# AgnusAdaptorEagle7.net
KiCad netlist of a schematic drawn in EAGLE
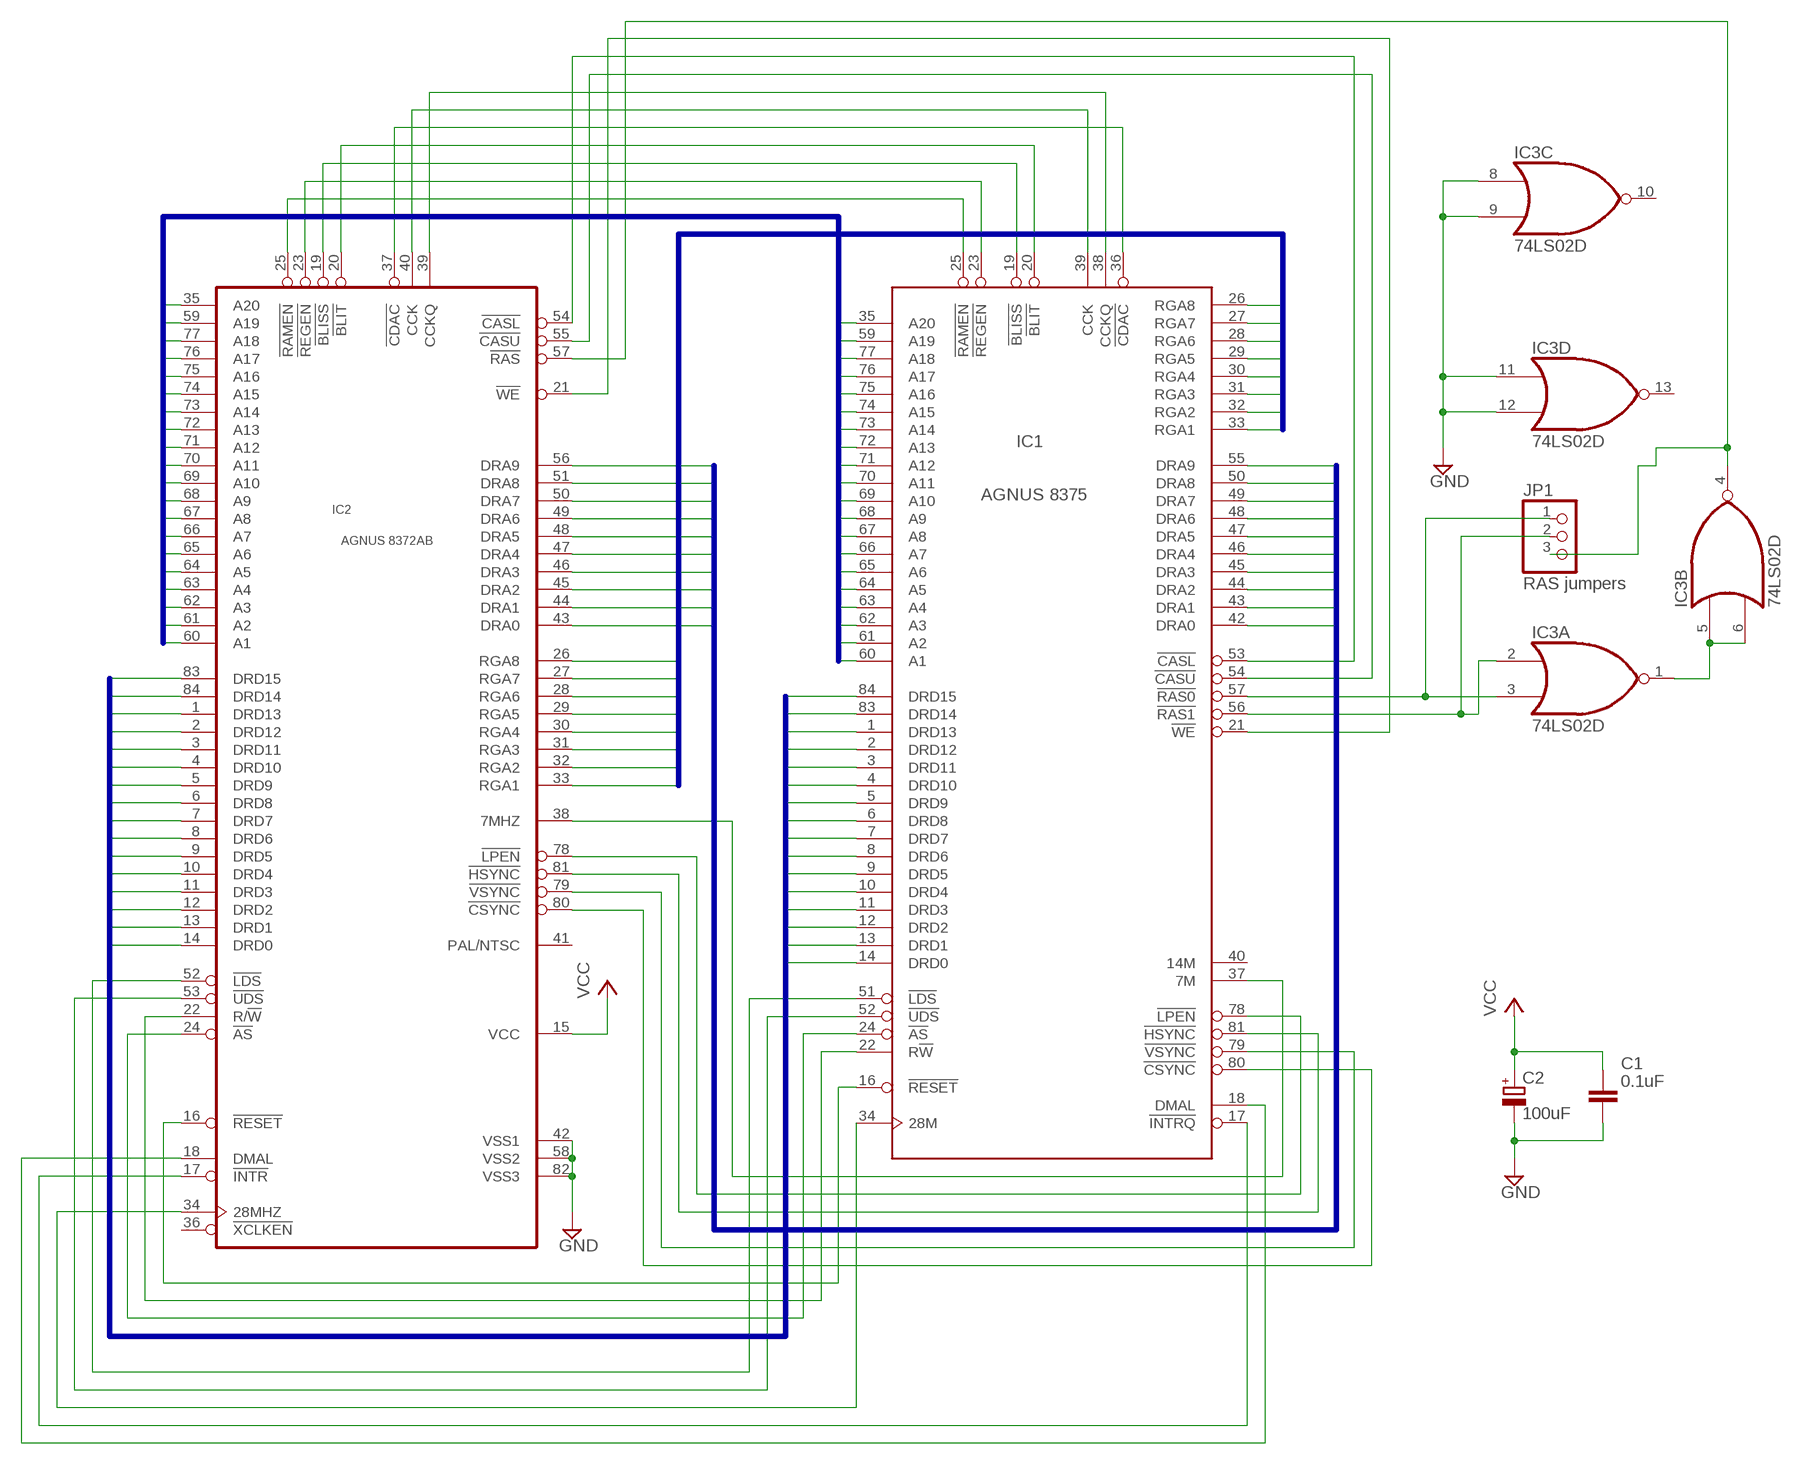
[diagram p0: schematic, sheet 1]

(export (version "E")
  (design (tool "Eeschema 10.0.6"))
  (components
    (comp (ref "C1")
      (value "0.1uF")
      (footprint "eagle-import:CAPC2012X110")
      (libsource (lib "eagle-import") (part "CCHIP-0805(2012-METRIC)_"))
    )
    (comp (ref "C2")
      (value "100uF")
      (footprint "eagle-import:CAPAE830X1050N")
      (libsource (lib "eagle-import") (part "C-POLECAP-8.5MM_"))
    )
    (comp (ref "IC1")
      (value "AGNUS_8375_A500+_A600_THT")
      (footprint "eagle-import:PLCC84_T")
      (libsource (lib "eagle-import") (part "AGNUS_8375_A500+_A600_THT"))
    )
    (comp (ref "IC2")
      (value "A3000 Agnus Socket")
      (footprint "eagle-import:PLCC84_T")
      (libsource (lib "eagle-import") (part "AGNUS_8372AB_THT"))
    )
    (comp (ref "IC3")
      (value "74LS02D")
      (footprint "eagle-import:SO14")
      (libsource (lib "eagle-import") (part "7402DLS"))
    )
    (comp (ref "JP1")
      (value "RAS jumpers")
      (footprint "eagle-import:1X03")
      (libsource (lib "eagle-import") (part "PINHD-1X3"))
    )
  )
  (nets
    (net (code "1") (name "/A1") (class "Default")
      (node (ref "IC1") (pin "60") (pinfunction "A1_60") (pintype "input"))
      (node (ref "IC2") (pin "60") (pinfunction "A1_60") (pintype "input"))
    )
    (net (code "2") (name "/A2") (class "Default")
      (node (ref "IC1") (pin "61") (pinfunction "A2_61") (pintype "input"))
      (node (ref "IC2") (pin "61") (pinfunction "A2_61") (pintype "input"))
    )
    (net (code "3") (name "/A3") (class "Default")
      (node (ref "IC1") (pin "62") (pinfunction "A3_62") (pintype "input"))
      (node (ref "IC2") (pin "62") (pinfunction "A3_62") (pintype "input"))
    )
    (net (code "4") (name "/A4") (class "Default")
      (node (ref "IC1") (pin "63") (pinfunction "A4_63") (pintype "input"))
      (node (ref "IC2") (pin "63") (pinfunction "A4_63") (pintype "input"))
    )
    (net (code "5") (name "/A5") (class "Default")
      (node (ref "IC1") (pin "64") (pinfunction "A5_64") (pintype "input"))
      (node (ref "IC2") (pin "64") (pinfunction "A5_64") (pintype "input"))
    )
    (net (code "6") (name "/A6") (class "Default")
      (node (ref "IC1") (pin "65") (pinfunction "A6_65") (pintype "input"))
      (node (ref "IC2") (pin "65") (pinfunction "A6_65") (pintype "input"))
    )
    (net (code "7") (name "/A7") (class "Default")
      (node (ref "IC1") (pin "66") (pinfunction "A7_66") (pintype "input"))
      (node (ref "IC2") (pin "66") (pinfunction "A7_66") (pintype "input"))
    )
    (net (code "8") (name "/A8") (class "Default")
      (node (ref "IC1") (pin "67") (pinfunction "A8_67") (pintype "input"))
      (node (ref "IC2") (pin "67") (pinfunction "A8_67") (pintype "input"))
    )
    (net (code "9") (name "/A9") (class "Default")
      (node (ref "IC1") (pin "68") (pinfunction "A9_68") (pintype "input"))
      (node (ref "IC2") (pin "68") (pinfunction "A9_68") (pintype "input"))
    )
    (net (code "10") (name "/A10") (class "Default")
      (node (ref "IC1") (pin "69") (pinfunction "A10_69") (pintype "input"))
      (node (ref "IC2") (pin "69") (pinfunction "A10_69") (pintype "input"))
    )
    (net (code "11") (name "/A11") (class "Default")
      (node (ref "IC1") (pin "70") (pinfunction "A11_70") (pintype "input"))
      (node (ref "IC2") (pin "70") (pinfunction "A11_70") (pintype "input"))
    )
    (net (code "12") (name "/A12") (class "Default")
      (node (ref "IC1") (pin "71") (pinfunction "A12_71") (pintype "input"))
      (node (ref "IC2") (pin "71") (pinfunction "A12_71") (pintype "input"))
    )
    (net (code "13") (name "/A13") (class "Default")
      (node (ref "IC1") (pin "72") (pinfunction "A13_72") (pintype "input"))
      (node (ref "IC2") (pin "72") (pinfunction "A13_72") (pintype "input"))
    )
    (net (code "14") (name "/A14") (class "Default")
      (node (ref "IC1") (pin "73") (pinfunction "A14_73") (pintype "input"))
      (node (ref "IC2") (pin "73") (pinfunction "A14_73") (pintype "input"))
    )
    (net (code "15") (name "/A15") (class "Default")
      (node (ref "IC1") (pin "74") (pinfunction "A15_74") (pintype "input"))
      (node (ref "IC2") (pin "74") (pinfunction "A15_74") (pintype "input"))
    )
    (net (code "16") (name "/A16") (class "Default")
      (node (ref "IC1") (pin "75") (pinfunction "A16_75") (pintype "input"))
      (node (ref "IC2") (pin "75") (pinfunction "A16_75") (pintype "input"))
    )
    (net (code "17") (name "/A17") (class "Default")
      (node (ref "IC1") (pin "76") (pinfunction "A17_76") (pintype "input"))
      (node (ref "IC2") (pin "76") (pinfunction "A17_76") (pintype "input"))
    )
    (net (code "18") (name "/A18") (class "Default")
      (node (ref "IC1") (pin "77") (pinfunction "A18_77") (pintype "input"))
      (node (ref "IC2") (pin "77") (pinfunction "A18_77") (pintype "input"))
    )
    (net (code "19") (name "/A19") (class "Default")
      (node (ref "IC1") (pin "59") (pinfunction "A19_59") (pintype "input"))
      (node (ref "IC2") (pin "59") (pinfunction "A19_59") (pintype "input"))
    )
    (net (code "20") (name "/A20") (class "Default")
      (node (ref "IC1") (pin "35") (pinfunction "A20_35") (pintype "input"))
      (node (ref "IC2") (pin "35") (pinfunction "A20_35") (pintype "input"))
    )
    (net (code "21") (name "/DRA0") (class "Default")
      (node (ref "IC1") (pin "42") (pinfunction "DRA0_42") (pintype "output"))
      (node (ref "IC2") (pin "43") (pinfunction "DRA0_43") (pintype "output"))
    )
    (net (code "22") (name "/DRA1") (class "Default")
      (node (ref "IC1") (pin "43") (pinfunction "DRA1_43") (pintype "output"))
      (node (ref "IC2") (pin "44") (pinfunction "DRA1_44") (pintype "output"))
    )
    (net (code "23") (name "/DRA2") (class "Default")
      (node (ref "IC1") (pin "44") (pinfunction "DRA2_44") (pintype "output"))
      (node (ref "IC2") (pin "45") (pinfunction "DRA2_45") (pintype "output"))
    )
    (net (code "24") (name "/DRA3") (class "Default")
      (node (ref "IC1") (pin "45") (pinfunction "DRA3_45") (pintype "output"))
      (node (ref "IC2") (pin "46") (pinfunction "DRA3_46") (pintype "output"))
    )
    (net (code "25") (name "/DRA4") (class "Default")
      (node (ref "IC1") (pin "46") (pinfunction "DRA4_46") (pintype "output"))
      (node (ref "IC2") (pin "47") (pinfunction "DRA4_47") (pintype "output"))
    )
    (net (code "26") (name "/DRA5") (class "Default")
      (node (ref "IC1") (pin "47") (pinfunction "DRA5_47") (pintype "output"))
      (node (ref "IC2") (pin "48") (pinfunction "DRA5_48") (pintype "output"))
    )
    (net (code "27") (name "/DRA6") (class "Default")
      (node (ref "IC1") (pin "48") (pinfunction "DRA6_48") (pintype "output"))
      (node (ref "IC2") (pin "49") (pinfunction "DRA6_49") (pintype "output"))
    )
    (net (code "28") (name "/DRA7") (class "Default")
      (node (ref "IC1") (pin "49") (pinfunction "DRA7_49") (pintype "output"))
      (node (ref "IC2") (pin "50") (pinfunction "DRA7_50") (pintype "output"))
    )
    (net (code "29") (name "/DRA8") (class "Default")
      (node (ref "IC1") (pin "50") (pinfunction "DRA8_50") (pintype "output"))
      (node (ref "IC2") (pin "51") (pinfunction "DRA8_51") (pintype "output"))
    )
    (net (code "30") (name "/DRA9") (class "Default")
      (node (ref "IC1") (pin "55") (pinfunction "DRA9_55") (pintype "output"))
      (node (ref "IC2") (pin "56") (pinfunction "DRA9_56") (pintype "output"))
    )
    (net (code "31") (name "/DRD0") (class "Default")
      (node (ref "IC1") (pin "14") (pinfunction "DRD0_14") (pintype "bidirectional"))
      (node (ref "IC2") (pin "14") (pinfunction "DRD0_14") (pintype "bidirectional"))
    )
    (net (code "32") (name "/DRD1") (class "Default")
      (node (ref "IC1") (pin "13") (pinfunction "DRD1_13") (pintype "bidirectional"))
      (node (ref "IC2") (pin "13") (pinfunction "DRD1_13") (pintype "bidirectional"))
    )
    (net (code "33") (name "/DRD2") (class "Default")
      (node (ref "IC1") (pin "12") (pinfunction "DRD2_12") (pintype "bidirectional"))
      (node (ref "IC2") (pin "12") (pinfunction "DRD2_12") (pintype "bidirectional"))
    )
    (net (code "34") (name "/DRD3") (class "Default")
      (node (ref "IC1") (pin "11") (pinfunction "DRD3_11") (pintype "bidirectional"))
      (node (ref "IC2") (pin "11") (pinfunction "DRD3_11") (pintype "bidirectional"))
    )
    (net (code "35") (name "/DRD4") (class "Default")
      (node (ref "IC1") (pin "10") (pinfunction "DRD4_10") (pintype "bidirectional"))
      (node (ref "IC2") (pin "10") (pinfunction "DRD4_10") (pintype "bidirectional"))
    )
    (net (code "36") (name "/DRD5") (class "Default")
      (node (ref "IC1") (pin "9") (pinfunction "DRD5_9") (pintype "bidirectional"))
      (node (ref "IC2") (pin "9") (pinfunction "DRD5_9") (pintype "bidirectional"))
    )
    (net (code "37") (name "/DRD6") (class "Default")
      (node (ref "IC1") (pin "8") (pinfunction "DRD6_8") (pintype "bidirectional"))
      (node (ref "IC2") (pin "8") (pinfunction "DRD6_8") (pintype "bidirectional"))
    )
    (net (code "38") (name "/DRD7") (class "Default")
      (node (ref "IC1") (pin "7") (pinfunction "DRD7_7") (pintype "bidirectional"))
      (node (ref "IC2") (pin "7") (pinfunction "DRD7_7") (pintype "bidirectional"))
    )
    (net (code "39") (name "/DRD8") (class "Default")
      (node (ref "IC1") (pin "6") (pinfunction "DRD8_6") (pintype "bidirectional"))
      (node (ref "IC2") (pin "6") (pinfunction "DRD8_6") (pintype "bidirectional"))
    )
    (net (code "40") (name "/DRD9") (class "Default")
      (node (ref "IC1") (pin "5") (pinfunction "DRD9_5") (pintype "bidirectional"))
      (node (ref "IC2") (pin "5") (pinfunction "DRD9_5") (pintype "bidirectional"))
    )
    (net (code "41") (name "/DRD10") (class "Default")
      (node (ref "IC1") (pin "4") (pinfunction "DRD10_4") (pintype "bidirectional"))
      (node (ref "IC2") (pin "4") (pinfunction "DRD10_4") (pintype "bidirectional"))
    )
    (net (code "42") (name "/DRD11") (class "Default")
      (node (ref "IC1") (pin "3") (pinfunction "DRD11_3") (pintype "bidirectional"))
      (node (ref "IC2") (pin "3") (pinfunction "DRD11_3") (pintype "bidirectional"))
    )
    (net (code "43") (name "/DRD12") (class "Default")
      (node (ref "IC1") (pin "2") (pinfunction "DRD12_2") (pintype "bidirectional"))
      (node (ref "IC2") (pin "2") (pinfunction "DRD12_2") (pintype "bidirectional"))
    )
    (net (code "44") (name "/DRD13") (class "Default")
      (node (ref "IC1") (pin "1") (pinfunction "DRD13_1") (pintype "bidirectional"))
      (node (ref "IC2") (pin "1") (pinfunction "DRD13_1") (pintype "bidirectional"))
    )
    (net (code "45") (name "/DRD14") (class "Default")
      (node (ref "IC1") (pin "83") (pinfunction "DRD14_83") (pintype "bidirectional"))
      (node (ref "IC2") (pin "84") (pinfunction "DRD14_84") (pintype "bidirectional"))
    )
    (net (code "46") (name "/DRD15") (class "Default")
      (node (ref "IC1") (pin "84") (pinfunction "DRD15_84") (pintype "bidirectional"))
      (node (ref "IC2") (pin "83") (pinfunction "DRD15_83") (pintype "bidirectional"))
    )
    (net (code "47") (name "/RGA1") (class "Default")
      (node (ref "IC1") (pin "33") (pinfunction "RGA1_33") (pintype "output"))
      (node (ref "IC2") (pin "33") (pinfunction "RGA1_33") (pintype "bidirectional"))
    )
    (net (code "48") (name "/RGA2") (class "Default")
      (node (ref "IC1") (pin "32") (pinfunction "RGA2_32") (pintype "output"))
      (node (ref "IC2") (pin "32") (pinfunction "RGA2_32") (pintype "bidirectional"))
    )
    (net (code "49") (name "/RGA3") (class "Default")
      (node (ref "IC1") (pin "31") (pinfunction "RGA3_31") (pintype "output"))
      (node (ref "IC2") (pin "31") (pinfunction "RGA3_31") (pintype "bidirectional"))
    )
    (net (code "50") (name "/RGA4") (class "Default")
      (node (ref "IC1") (pin "30") (pinfunction "RGA4_30") (pintype "output"))
      (node (ref "IC2") (pin "30") (pinfunction "RGA4_30") (pintype "bidirectional"))
    )
    (net (code "51") (name "/RGA5") (class "Default")
      (node (ref "IC1") (pin "29") (pinfunction "RGA5_29") (pintype "output"))
      (node (ref "IC2") (pin "29") (pinfunction "RGA5_29") (pintype "bidirectional"))
    )
    (net (code "52") (name "/RGA6") (class "Default")
      (node (ref "IC1") (pin "28") (pinfunction "RGA6_28") (pintype "output"))
      (node (ref "IC2") (pin "28") (pinfunction "RGA6_28") (pintype "bidirectional"))
    )
    (net (code "53") (name "/RGA7") (class "Default")
      (node (ref "IC1") (pin "27") (pinfunction "RGA7_27") (pintype "output"))
      (node (ref "IC2") (pin "27") (pinfunction "RGA7_27") (pintype "bidirectional"))
    )
    (net (code "54") (name "/RGA8") (class "Default")
      (node (ref "IC1") (pin "26") (pinfunction "RGA8_26") (pintype "output"))
      (node (ref "IC2") (pin "26") (pinfunction "RGA8_26") (pintype "bidirectional"))
    )
    (net (code "55") (name "GND") (class "Default")
      (node (ref "C1") (pin "2") (pinfunction "2_2") (pintype "passive"))
      (node (ref "C2") (pin "2") (pinfunction "-_2") (pintype "passive"))
      (node (ref "IC2") (pin "42") (pinfunction "VSS1_42") (pintype "power_in"))
      (node (ref "IC2") (pin "58") (pinfunction "VSS2_58") (pintype "power_in"))
      (node (ref "IC2") (pin "82") (pinfunction "VSS3_82") (pintype "power_in"))
      (node (ref "IC3") (pin "11") (pinfunction "I0_11") (pintype "input"))
      (node (ref "IC3") (pin "12") (pinfunction "I1_12") (pintype "input"))
      (node (ref "IC3") (pin "8") (pinfunction "I0_8") (pintype "input"))
      (node (ref "IC3") (pin "9") (pinfunction "I1_9") (pintype "input"))
    )
    (net (code "56") (name "Net-(IC1A-7M)") (class "Default")
      (node (ref "IC1") (pin "37") (pinfunction "7M_37") (pintype "output"))
      (node (ref "IC2") (pin "38") (pinfunction "7MHZ_38") (pintype "output"))
    )
    (net (code "57") (name "Net-(IC1A-28M)") (class "Default")
      (node (ref "IC1") (pin "34") (pinfunction "28M_34") (pintype "input"))
      (node (ref "IC2") (pin "34") (pinfunction "28MHZ_34") (pintype "input"))
    )
    (net (code "58") (name "Net-(IC1A-CCK)") (class "Default")
      (node (ref "IC1") (pin "39") (pinfunction "CCK_39") (pintype "output"))
      (node (ref "IC2") (pin "40") (pinfunction "CCK_40") (pintype "output"))
    )
    (net (code "59") (name "Net-(IC1A-CCKQ)") (class "Default")
      (node (ref "IC1") (pin "38") (pinfunction "CCKQ_38") (pintype "output"))
      (node (ref "IC2") (pin "39") (pinfunction "CCKQ_39") (pintype "output"))
    )
    (net (code "60") (name "Net-(IC1A-DMAL)") (class "Default")
      (node (ref "IC1") (pin "18") (pinfunction "DMAL_18") (pintype "input"))
      (node (ref "IC2") (pin "18") (pinfunction "DMAL_18") (pintype "input"))
    )
    (net (code "61") (name "Net-(IC1A-R~{W})") (class "Default")
      (node (ref "IC1") (pin "22") (pinfunction "R~{W}_22") (pintype "input"))
      (node (ref "IC2") (pin "22") (pinfunction "R/~{W}_22") (pintype "input"))
    )
    (net (code "62") (name "Net-(IC1A-~{AS})") (class "Default")
      (node (ref "IC1") (pin "24") (pinfunction "~{AS}_24") (pintype "input"))
      (node (ref "IC2") (pin "24") (pinfunction "~{AS}_24") (pintype "input"))
    )
    (net (code "63") (name "Net-(IC1A-~{BLISS})") (class "Default")
      (node (ref "IC1") (pin "19") (pinfunction "~{BLISS}_19") (pintype "output"))
      (node (ref "IC2") (pin "19") (pinfunction "~{BLISS}_19") (pintype "input"))
    )
    (net (code "64") (name "Net-(IC1A-~{BLIT})") (class "Default")
      (node (ref "IC1") (pin "20") (pinfunction "~{BLIT}_20") (pintype "output"))
      (node (ref "IC2") (pin "20") (pinfunction "~{BLIT}_20") (pintype "output"))
    )
    (net (code "65") (name "Net-(IC1A-~{CASL})") (class "Default")
      (node (ref "IC1") (pin "53") (pinfunction "~{CASL}_53") (pintype "output"))
      (node (ref "IC2") (pin "54") (pinfunction "~{CASL}_54") (pintype "output"))
    )
    (net (code "66") (name "Net-(IC1A-~{CASU})") (class "Default")
      (node (ref "IC1") (pin "54") (pinfunction "~{CASU}_54") (pintype "output"))
      (node (ref "IC2") (pin "55") (pinfunction "~{CASU}_55") (pintype "output"))
    )
    (net (code "67") (name "Net-(IC1A-~{CDAC})") (class "Default")
      (node (ref "IC1") (pin "36") (pinfunction "~{CDAC}_36") (pintype "output"))
      (node (ref "IC2") (pin "37") (pinfunction "~{CDAC}_37") (pintype "output"))
    )
    (net (code "68") (name "Net-(IC1A-~{CSYNC})") (class "Default")
      (node (ref "IC1") (pin "80") (pinfunction "~{CSYNC}_80") (pintype "output"))
      (node (ref "IC2") (pin "80") (pinfunction "~{CSYNC}_80") (pintype "output"))
    )
    (net (code "69") (name "Net-(IC1A-~{HSYNC})") (class "Default")
      (node (ref "IC1") (pin "81") (pinfunction "~{HSYNC}_81") (pintype "output"))
      (node (ref "IC2") (pin "81") (pinfunction "~{HSYNC}_81") (pintype "output"))
    )
    (net (code "70") (name "Net-(IC1A-~{INTRQ})") (class "Default")
      (node (ref "IC1") (pin "17") (pinfunction "~{INTRQ}_17") (pintype "output"))
      (node (ref "IC2") (pin "17") (pinfunction "~{INTR}_17") (pintype "output"))
    )
    (net (code "71") (name "Net-(IC1A-~{LDS})") (class "Default")
      (node (ref "IC1") (pin "51") (pinfunction "~{LDS}_51") (pintype "input"))
      (node (ref "IC2") (pin "52") (pinfunction "~{LDS}_52") (pintype "input"))
    )
    (net (code "72") (name "Net-(IC1A-~{LPEN})") (class "Default")
      (node (ref "IC1") (pin "78") (pinfunction "~{LPEN}_78") (pintype "input"))
      (node (ref "IC2") (pin "78") (pinfunction "~{LPEN}_78") (pintype "input"))
    )
    (net (code "73") (name "Net-(IC1A-~{RAMEN})") (class "Default")
      (node (ref "IC1") (pin "25") (pinfunction "~{RAMEN}_25") (pintype "output"))
      (node (ref "IC2") (pin "25") (pinfunction "~{RAMEN}_25") (pintype "input"))
    )
    (net (code "74") (name "Net-(IC1A-~{RAS0})") (class "Default")
      (node (ref "IC1") (pin "57") (pinfunction "~{RAS0}_57") (pintype "output"))
      (node (ref "IC3") (pin "3") (pinfunction "I1_3") (pintype "input"))
      (node (ref "JP1") (pin "1") (pinfunction "1_1") (pintype "passive"))
    )
    (net (code "75") (name "Net-(IC1A-~{RAS1})") (class "Default")
      (node (ref "IC1") (pin "56") (pinfunction "~{RAS1}_56") (pintype "output"))
      (node (ref "IC3") (pin "2") (pinfunction "I0_2") (pintype "input"))
      (node (ref "JP1") (pin "2") (pinfunction "2_2") (pintype "passive"))
    )
    (net (code "76") (name "Net-(IC1A-~{REGEN})") (class "Default")
      (node (ref "IC1") (pin "23") (pinfunction "~{REGEN}_23") (pintype "output"))
      (node (ref "IC2") (pin "23") (pinfunction "~{REGEN}_23") (pintype "input"))
    )
    (net (code "77") (name "Net-(IC1A-~{RESET})") (class "Default")
      (node (ref "IC1") (pin "16") (pinfunction "~{RESET}_16") (pintype "input"))
      (node (ref "IC2") (pin "16") (pinfunction "~{RESET}_16") (pintype "input"))
    )
    (net (code "78") (name "Net-(IC1A-~{UDS})") (class "Default")
      (node (ref "IC1") (pin "52") (pinfunction "~{UDS}_52") (pintype "input"))
      (node (ref "IC2") (pin "53") (pinfunction "~{UDS}_53") (pintype "input"))
    )
    (net (code "79") (name "Net-(IC1A-~{VSYNC})") (class "Default")
      (node (ref "IC1") (pin "79") (pinfunction "~{VSYNC}_79") (pintype "output"))
      (node (ref "IC2") (pin "79") (pinfunction "~{VSYNC}_79") (pintype "output"))
    )
    (net (code "80") (name "Net-(IC1A-~{WE})") (class "Default")
      (node (ref "IC1") (pin "21") (pinfunction "~{WE}_21") (pintype "output"))
      (node (ref "IC2") (pin "21") (pinfunction "~{WE}_21") (pintype "output"))
    )
    (net (code "81") (name "Net-(IC2-~{RAS})") (class "Default")
      (node (ref "IC2") (pin "57") (pinfunction "~{RAS}_57") (pintype "output"))
      (node (ref "IC3") (pin "4") (pinfunction "O_4") (pintype "output"))
      (node (ref "JP1") (pin "3") (pinfunction "3_3") (pintype "passive"))
    )
    (net (code "82") (name "Net-(IC3A-O)") (class "Default")
      (node (ref "IC3") (pin "1") (pinfunction "O_1") (pintype "output"))
      (node (ref "IC3") (pin "5") (pinfunction "I0_5") (pintype "input"))
      (node (ref "IC3") (pin "6") (pinfunction "I1_6") (pintype "input"))
    )
    (net (code "83") (name "VCC") (class "Default")
      (node (ref "C1") (pin "1") (pinfunction "1_1") (pintype "passive"))
      (node (ref "C2") (pin "1") (pinfunction "+_1") (pintype "passive"))
      (node (ref "IC2") (pin "15") (pinfunction "VCC_15") (pintype "power_in"))
    )
    (net (code "84") (name "unconnected-(IC1A-14M-Pad40)") (class "Default")
      (node (ref "IC1") (pin "40") (pinfunction "14M_40") (pintype "output"))
    )
    (net (code "85") (name "unconnected-(IC2-PAL{slash}NTSC-Pad41)") (class "Default")
      (node (ref "IC2") (pin "41") (pinfunction "PAL/NTSC_41") (pintype "input"))
    )
    (net (code "86") (name "unconnected-(IC2-~{XCLKEN}-Pad36)") (class "Default")
      (node (ref "IC2") (pin "36") (pinfunction "~{XCLKEN}_36") (pintype "input"))
    )
    (net (code "87") (name "unconnected-(IC3C-O-Pad10)") (class "Default")
      (node (ref "IC3") (pin "10") (pinfunction "O_10") (pintype "output"))
    )
    (net (code "88") (name "unconnected-(IC3D-O-Pad13)") (class "Default")
      (node (ref "IC3") (pin "13") (pinfunction "O_13") (pintype "output"))
    )
  )
)
